# Sheet1.net
KiCad netlist of a schematic drawn in Altium Designer
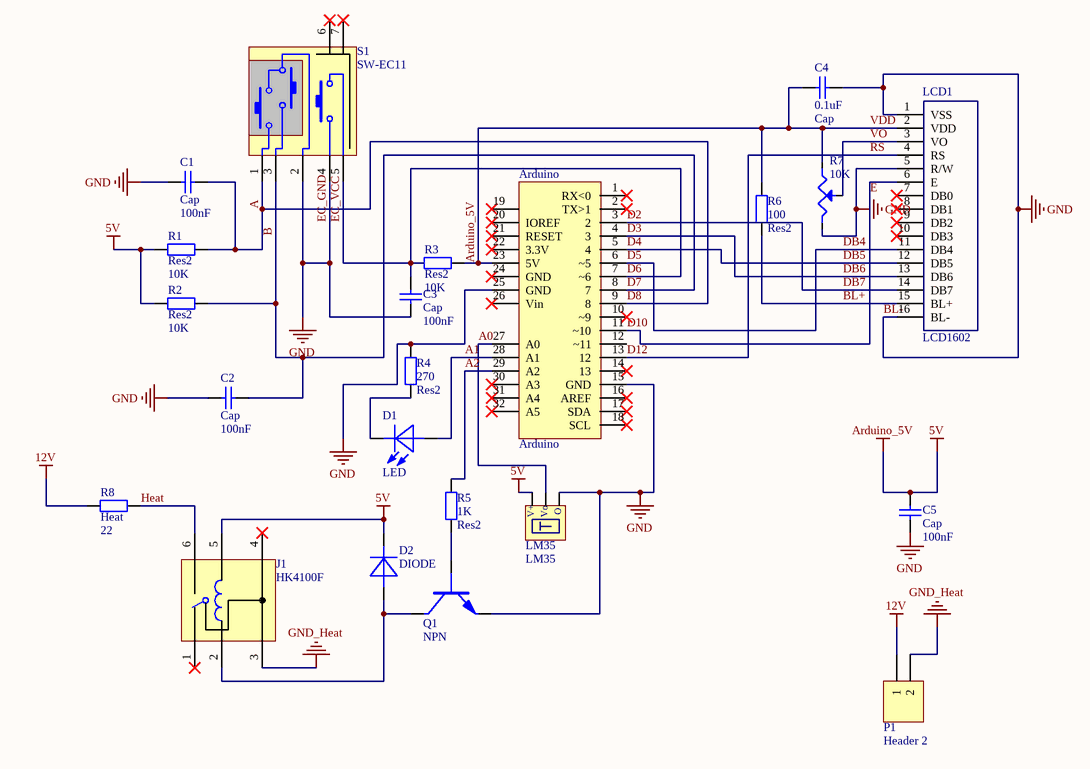
[diagram p0: Sheet1.SchDoc]

(export (version "E")
  (design (tool "Eeschema 10.0.6"))
  (components
    (comp (ref "Arduino")
      (value "Arduino")
      (footprint "Arduino-UNO")
      (libsource (lib "LixhSch") (part "Arduino-UNO"))
    )
    (comp (ref "C1")
      (value "Cap")
      (footprint "RAD-0.3")
      (description "Capacitor")
      (fields (field (name "ALTIUM_VALUE") "100nF") (field (name "PUBLISHER") "Altium Limited"))
      (libsource (lib "Miscellaneous Devices") (part "Cap"))
    )
    (comp (ref "C2")
      (value "Cap")
      (footprint "RAD-0.3")
      (description "Capacitor")
      (fields (field (name "ALTIUM_VALUE") "100nF") (field (name "PUBLISHER") "Altium Limited"))
      (libsource (lib "Miscellaneous Devices") (part "Cap"))
    )
    (comp (ref "C3")
      (value "Cap")
      (footprint "RAD-0.3")
      (description "Capacitor")
      (fields (field (name "ALTIUM_VALUE") "100nF") (field (name "PUBLISHER") "Altium Limited"))
      (libsource (lib "Miscellaneous Devices") (part "Cap"))
    )
    (comp (ref "C4")
      (value "Cap")
      (footprint "RAD-0.3")
      (description "Capacitor")
      (fields (field (name "ALTIUM_VALUE") "0.1uF") (field (name "PUBLISHER") "Altium Limited"))
      (libsource (lib "Miscellaneous Devices") (part "Cap"))
    )
    (comp (ref "C5")
      (value "Cap")
      (footprint "RAD-0.3")
      (description "Capacitor")
      (fields (field (name "ALTIUM_VALUE") "100nF") (field (name "PUBLISHER") "Altium Limited"))
      (libsource (lib "Miscellaneous Devices") (part "Cap"))
    )
    (comp (ref "D1")
      (value "LED")
      (footprint "LEDLXH-5")
      (description "发光二极管")
      (libsource (lib "LixhSch") (part "LEDLXH"))
    )
    (comp (ref "D2")
      (value "DIODE")
      (footprint "DIODE-4")
      (description "Diode")
      (libsource (lib "LixhSch") (part "DIODELXH"))
    )
    (comp (ref "J1")
      (value "HK4100F")
      (footprint "HK4100F")
      (description "单刀双掷继电器")
      (libsource (lib "Fszhang") (part "HK4100F"))
    )
    (comp (ref "LCD1") (value "LCD1602") (footprint "LCD1602") (libsource (lib "LCD") (part "LCD1602")))
    (comp (ref "LM35")
      (value "LM35")
      (footprint "LM35")
      (description "LM35温度传感器")
      (libsource (lib "LixhSch") (part "LM35"))
    )
    (comp (ref "P1")
      (value "Header 2")
      (footprint "POWER PLUG2")
      (description "Header, 2-Pin")
      (fields (field (name "PUBLISHER") "Altium Limited"))
      (libsource (lib "Miscellaneous Connectors") (part "Header 2"))
    )
    (comp (ref "Q1")
      (value "NPN")
      (footprint "NPN-2")
      (description "NPN Transistor")
      (libsource (lib "LixhSch") (part "NPNLXH"))
    )
    (comp (ref "R1")
      (value "Res2")
      (footprint "AXIAL-0.4")
      (description "Resistor")
      (fields (field (name "ALTIUM_VALUE") "10K") (field (name "PUBLISHER") "Altium Limited"))
      (libsource (lib "Miscellaneous Devices") (part "Res2"))
    )
    (comp (ref "R2")
      (value "Res2")
      (footprint "AXIAL-0.4")
      (description "Resistor")
      (fields (field (name "ALTIUM_VALUE") "10K") (field (name "PUBLISHER") "Altium Limited"))
      (libsource (lib "Miscellaneous Devices") (part "Res2"))
    )
    (comp (ref "R3")
      (value "Res2")
      (footprint "AXIAL-0.4")
      (description "Resistor")
      (fields (field (name "ALTIUM_VALUE") "10K") (field (name "PUBLISHER") "Altium Limited"))
      (libsource (lib "Miscellaneous Devices") (part "Res2"))
    )
    (comp (ref "R4")
      (value "Res2")
      (footprint "AXIAL-0.4")
      (description "Resistor")
      (fields (field (name "ALTIUM_VALUE") "270") (field (name "PUBLISHER") "Altium Limited"))
      (libsource (lib "") (part "Res2_1"))
    )
    (comp (ref "R5")
      (value "Res2")
      (footprint "AXIAL-0.4")
      (description "Resistor")
      (fields (field (name "ALTIUM_VALUE") "1K") (field (name "PUBLISHER") "Altium Limited"))
      (libsource (lib "") (part "Res2_1"))
    )
    (comp (ref "R6")
      (value "Res2")
      (footprint "AXIAL-0.4")
      (description "Resistor")
      (fields (field (name "ALTIUM_VALUE") "100") (field (name "PUBLISHER") "Altium Limited"))
      (libsource (lib "") (part "Res2_1"))
    )
    (comp (ref "R7")
      (value "10K")
      (footprint "VR-5")
      (description "Potentiometer")
      (libsource (lib "Miscellaneous Devices") (part "POT1"))
    )
    (comp (ref "R8")
      (value "Heat")
      (footprint "AXIAL4cm")
      (description "Resistor")
      (fields (field (name "ALTIUM_VALUE") "22") (field (name "PUBLISHER") "Altium Limited"))
      (libsource (lib "") (part "Res2_2"))
    )
    (comp (ref "S1")
      (value "SW-EC11")
      (footprint "EC11")
      (description "旋转编码开关")
      (fields (field (name "PUBLISHER") "Altium Limited"))
      (libsource (lib "LixhSch") (part "SW-EC11"))
    )
  )
  (nets
    (net (code "1") (name "/A") (class "Default")
      (node (ref "Arduino") (pin "9") (pinfunction "8_9") (pintype "power_in"))
      (node (ref "C1") (pin "1") (pinfunction "1_1") (pintype "passive"))
      (node (ref "R1") (pin "2") (pinfunction "2_2") (pintype "passive"))
      (node (ref "S1") (pin "1") (pinfunction "1_1") (pintype "passive"))
    )
    (net (code "2") (name "/A0") (class "Default")
      (node (ref "Arduino") (pin "27") (pinfunction "A0_27") (pintype "power_in"))
      (node (ref "LM35") (pin "2") (pinfunction "2_2") (pintype "passive"))
    )
    (net (code "3") (name "/A1") (class "Default")
      (node (ref "Arduino") (pin "28") (pinfunction "A1_28") (pintype "power_in"))
      (node (ref "D1") (pin "1") (pinfunction "A_1") (pintype "passive"))
    )
    (net (code "4") (name "/A2") (class "Default")
      (node (ref "Arduino") (pin "29") (pinfunction "A2_29") (pintype "power_in"))
      (node (ref "R5") (pin "2") (pinfunction "2_2") (pintype "passive"))
    )
    (net (code "5") (name "/B") (class "Default")
      (node (ref "Arduino") (pin "8") (pinfunction "7_8") (pintype "power_in"))
      (node (ref "C2") (pin "1") (pinfunction "1_1") (pintype "passive"))
      (node (ref "R2") (pin "2") (pinfunction "2_2") (pintype "passive"))
      (node (ref "S1") (pin "3") (pinfunction "3_3") (pintype "passive"))
    )
    (net (code "6") (name "/BL+") (class "Default")
      (node (ref "LCD1") (pin "15") (pinfunction "BL+_15") (pintype "passive"))
      (node (ref "R6") (pin "1") (pinfunction "1_1") (pintype "passive"))
    )
    (net (code "7") (name "/D2") (class "Default")
      (node (ref "Arduino") (pin "3") (pinfunction "2_3") (pintype "power_in"))
      (node (ref "LCD1") (pin "14") (pinfunction "DB7_14") (pintype "passive"))
    )
    (net (code "8") (name "/D3") (class "Default")
      (node (ref "Arduino") (pin "4") (pinfunction "3_4") (pintype "power_in"))
      (node (ref "LCD1") (pin "13") (pinfunction "DB6_13") (pintype "passive"))
    )
    (net (code "9") (name "/D4") (class "Default")
      (node (ref "Arduino") (pin "5") (pinfunction "4_5") (pintype "power_in"))
      (node (ref "LCD1") (pin "12") (pinfunction "DB5_12") (pintype "passive"))
    )
    (net (code "10") (name "/D5") (class "Default")
      (node (ref "Arduino") (pin "6") (pinfunction "~5_6") (pintype "power_in"))
      (node (ref "LCD1") (pin "11") (pinfunction "DB4_11") (pintype "passive"))
    )
    (net (code "11") (name "/D6") (class "Default")
      (node (ref "Arduino") (pin "7") (pinfunction "~6_7") (pintype "power_in"))
      (node (ref "C3") (pin "2") (pinfunction "2_2") (pintype "passive"))
      (node (ref "R3") (pin "1") (pinfunction "1_1") (pintype "passive"))
      (node (ref "S1") (pin "5") (pinfunction "5_5") (pintype "passive"))
    )
    (net (code "12") (name "/D10") (class "Default")
      (node (ref "Arduino") (pin "11") (pinfunction "~10_11") (pintype "power_in"))
      (node (ref "LCD1") (pin "6") (pinfunction "E_6") (pintype "passive"))
    )
    (net (code "13") (name "/D12") (class "Default")
      (node (ref "Arduino") (pin "13") (pinfunction "12_13") (pintype "power_in"))
      (node (ref "LCD1") (pin "4") (pinfunction "RS_4") (pintype "passive"))
    )
    (net (code "14") (name "/Heat") (class "Default")
      (node (ref "J1") (pin "6") (pinfunction "6_6") (pintype "passive"))
      (node (ref "R8") (pin "1") (pinfunction "1_1") (pintype "passive"))
    )
    (net (code "15") (name "/VO") (class "Default")
      (node (ref "LCD1") (pin "3") (pinfunction "VO_3") (pintype "passive"))
      (node (ref "R7") (pin "3") (pinfunction "W_3") (pintype "passive"))
    )
    (net (code "16") (name "5V") (class "Default")
      (node (ref "Arduino") (pin "23") (pinfunction "5V_23") (pintype "power_in"))
      (node (ref "C4") (pin "2") (pinfunction "2_2") (pintype "passive"))
      (node (ref "C5") (pin "1") (pinfunction "1_1") (pintype "passive"))
      (node (ref "D2") (pin "2") (pinfunction "K_2") (pintype "passive"))
      (node (ref "J1") (pin "5") (pinfunction "5_5") (pintype "passive"))
      (node (ref "LCD1") (pin "2") (pinfunction "VDD_2") (pintype "passive"))
      (node (ref "LM35") (pin "1") (pinfunction "1_1") (pintype "power_in"))
      (node (ref "R1") (pin "1") (pinfunction "1_1") (pintype "passive"))
      (node (ref "R2") (pin "1") (pinfunction "1_1") (pintype "passive"))
      (node (ref "R3") (pin "2") (pinfunction "2_2") (pintype "passive"))
      (node (ref "R6") (pin "2") (pinfunction "2_2") (pintype "passive"))
      (node (ref "R7") (pin "1") (pinfunction "1_1") (pintype "passive"))
    )
    (net (code "17") (name "12V") (class "Default")
      (node (ref "P1") (pin "1") (pinfunction "1_1") (pintype "passive"))
      (node (ref "R8") (pin "2") (pinfunction "2_2") (pintype "passive"))
    )
    (net (code "18") (name "GND") (class "Default")
      (node (ref "Arduino") (pin "15") (pinfunction "GND_15") (pintype "power_in"))
      (node (ref "Arduino") (pin "25") (pinfunction "GND_25") (pintype "power_in"))
      (node (ref "C1") (pin "2") (pinfunction "2_2") (pintype "passive"))
      (node (ref "C2") (pin "2") (pinfunction "2_2") (pintype "passive"))
      (node (ref "C3") (pin "1") (pinfunction "1_1") (pintype "passive"))
      (node (ref "C4") (pin "1") (pinfunction "1_1") (pintype "passive"))
      (node (ref "C5") (pin "2") (pinfunction "2_2") (pintype "passive"))
      (node (ref "LCD1") (pin "1") (pinfunction "VSS_1") (pintype "passive"))
      (node (ref "LCD1") (pin "16") (pinfunction "BL-_16") (pintype "passive"))
      (node (ref "LCD1") (pin "5") (pinfunction "R/W_5") (pintype "passive"))
      (node (ref "LM35") (pin "3") (pinfunction "3_3") (pintype "power_in"))
      (node (ref "Q1") (pin "1") (pinfunction "E_1") (pintype "passive"))
      (node (ref "R4") (pin "2") (pinfunction "2_2") (pintype "passive"))
      (node (ref "R7") (pin "2") (pinfunction "2_2") (pintype "passive"))
      (node (ref "S1") (pin "2") (pinfunction "2_2") (pintype "passive"))
      (node (ref "S1") (pin "4") (pinfunction "4_4") (pintype "passive"))
    )
    (net (code "19") (name "GND_Heat") (class "Default")
      (node (ref "J1") (pin "3") (pinfunction "3_3") (pintype "passive"))
      (node (ref "P1") (pin "2") (pinfunction "2_2") (pintype "passive"))
    )
    (net (code "20") (name "Net-(D1-K)") (class "Default")
      (node (ref "D1") (pin "2") (pinfunction "K_2") (pintype "passive"))
      (node (ref "R4") (pin "1") (pinfunction "1_1") (pintype "passive"))
    )
    (net (code "21") (name "Net-(D2-A)") (class "Default")
      (node (ref "D2") (pin "1") (pinfunction "A_1") (pintype "passive"))
      (node (ref "J1") (pin "2") (pinfunction "2_2") (pintype "passive"))
      (node (ref "Q1") (pin "3") (pinfunction "C_3") (pintype "passive"))
    )
    (net (code "22") (name "Net-(Q1-B)") (class "Default")
      (node (ref "Q1") (pin "2") (pinfunction "B_2") (pintype "passive"))
      (node (ref "R5") (pin "1") (pinfunction "1_1") (pintype "passive"))
    )
    (net (code "23") (name "unconnected-(Arduino-3.3V-Pad22)") (class "Default")
      (node (ref "Arduino") (pin "22") (pinfunction "3.3V_22") (pintype "power_in+no_connect"))
    )
    (net (code "24") (name "unconnected-(Arduino-13-Pad14)") (class "Default")
      (node (ref "Arduino") (pin "14") (pinfunction "13_14") (pintype "power_in+no_connect"))
    )
    (net (code "25") (name "unconnected-(Arduino-A3-Pad30)") (class "Default")
      (node (ref "Arduino") (pin "30") (pinfunction "A3_30") (pintype "power_in+no_connect"))
    )
    (net (code "26") (name "unconnected-(Arduino-A4-Pad31)") (class "Default")
      (node (ref "Arduino") (pin "31") (pinfunction "A4_31") (pintype "power_in+no_connect"))
    )
    (net (code "27") (name "unconnected-(Arduino-A5-Pad32)") (class "Default")
      (node (ref "Arduino") (pin "32") (pinfunction "A5_32") (pintype "power_in+no_connect"))
    )
    (net (code "28") (name "unconnected-(Arduino-AREF-Pad16)") (class "Default")
      (node (ref "Arduino") (pin "16") (pinfunction "AREF_16") (pintype "power_in+no_connect"))
    )
    (net (code "29") (name "unconnected-(Arduino-GND-Pad24)") (class "Default")
      (node (ref "Arduino") (pin "24") (pinfunction "GND_24") (pintype "power_in+no_connect"))
    )
    (net (code "30") (name "unconnected-(Arduino-IOREF-Pad20)") (class "Default")
      (node (ref "Arduino") (pin "20") (pinfunction "IOREF_20") (pintype "power_in+no_connect"))
    )
    (net (code "31") (name "unconnected-(Arduino-Pad19)") (class "Default")
      (node (ref "Arduino") (pin "19") (pintype "power_in+no_connect"))
    )
    (net (code "32") (name "unconnected-(Arduino-RESET-Pad21)") (class "Default")
      (node (ref "Arduino") (pin "21") (pinfunction "RESET_21") (pintype "power_in+no_connect"))
    )
    (net (code "33") (name "unconnected-(Arduino-RX<0-Pad1)") (class "Default")
      (node (ref "Arduino") (pin "1") (pinfunction "RX<0_1") (pintype "power_in+no_connect"))
    )
    (net (code "34") (name "unconnected-(Arduino-SCL-Pad18)") (class "Default")
      (node (ref "Arduino") (pin "18") (pinfunction "SCL_18") (pintype "power_in+no_connect"))
    )
    (net (code "35") (name "unconnected-(Arduino-SDA-Pad17)") (class "Default")
      (node (ref "Arduino") (pin "17") (pinfunction "SDA_17") (pintype "power_in+no_connect"))
    )
    (net (code "36") (name "unconnected-(Arduino-TX>1-Pad2)") (class "Default")
      (node (ref "Arduino") (pin "2") (pinfunction "TX>1_2") (pintype "power_in+no_connect"))
    )
    (net (code "37") (name "unconnected-(Arduino-Vin-Pad26)") (class "Default")
      (node (ref "Arduino") (pin "26") (pinfunction "Vin_26") (pintype "power_in+no_connect"))
    )
    (net (code "38") (name "unconnected-(Arduino-~9-Pad10)") (class "Default")
      (node (ref "Arduino") (pin "10") (pinfunction "~9_10") (pintype "power_in+no_connect"))
    )
    (net (code "39") (name "unconnected-(Arduino-~11-Pad12)") (class "Default")
      (node (ref "Arduino") (pin "12") (pinfunction "~11_12") (pintype "power_in"))
    )
    (net (code "40") (name "unconnected-(J1-Pad1)") (class "Default")
      (node (ref "J1") (pin "1") (pinfunction "1_1") (pintype "passive+no_connect"))
    )
    (net (code "41") (name "unconnected-(J1-Pad4)") (class "Default")
      (node (ref "J1") (pin "4") (pinfunction "4_4") (pintype "passive+no_connect"))
    )
    (net (code "42") (name "unconnected-(LCD1-DB0-Pad7)") (class "Default")
      (node (ref "LCD1") (pin "7") (pinfunction "DB0_7") (pintype "passive+no_connect"))
    )
    (net (code "43") (name "unconnected-(LCD1-DB1-Pad8)") (class "Default")
      (node (ref "LCD1") (pin "8") (pinfunction "DB1_8") (pintype "passive+no_connect"))
    )
    (net (code "44") (name "unconnected-(LCD1-DB2-Pad9)") (class "Default")
      (node (ref "LCD1") (pin "9") (pinfunction "DB2_9") (pintype "passive+no_connect"))
    )
    (net (code "45") (name "unconnected-(LCD1-DB3-Pad10)") (class "Default")
      (node (ref "LCD1") (pin "10") (pinfunction "DB3_10") (pintype "passive+no_connect"))
    )
    (net (code "46") (name "unconnected-(S1-Pad6)") (class "Default")
      (node (ref "S1") (pin "6") (pinfunction "6_6") (pintype "passive+no_connect"))
    )
    (net (code "47") (name "unconnected-(S1-Pad7)") (class "Default")
      (node (ref "S1") (pin "7") (pinfunction "7_7") (pintype "passive+no_connect"))
    )
  )
)
